# 00A-050.net
KiCad netlist of a schematic drawn in EAGLE
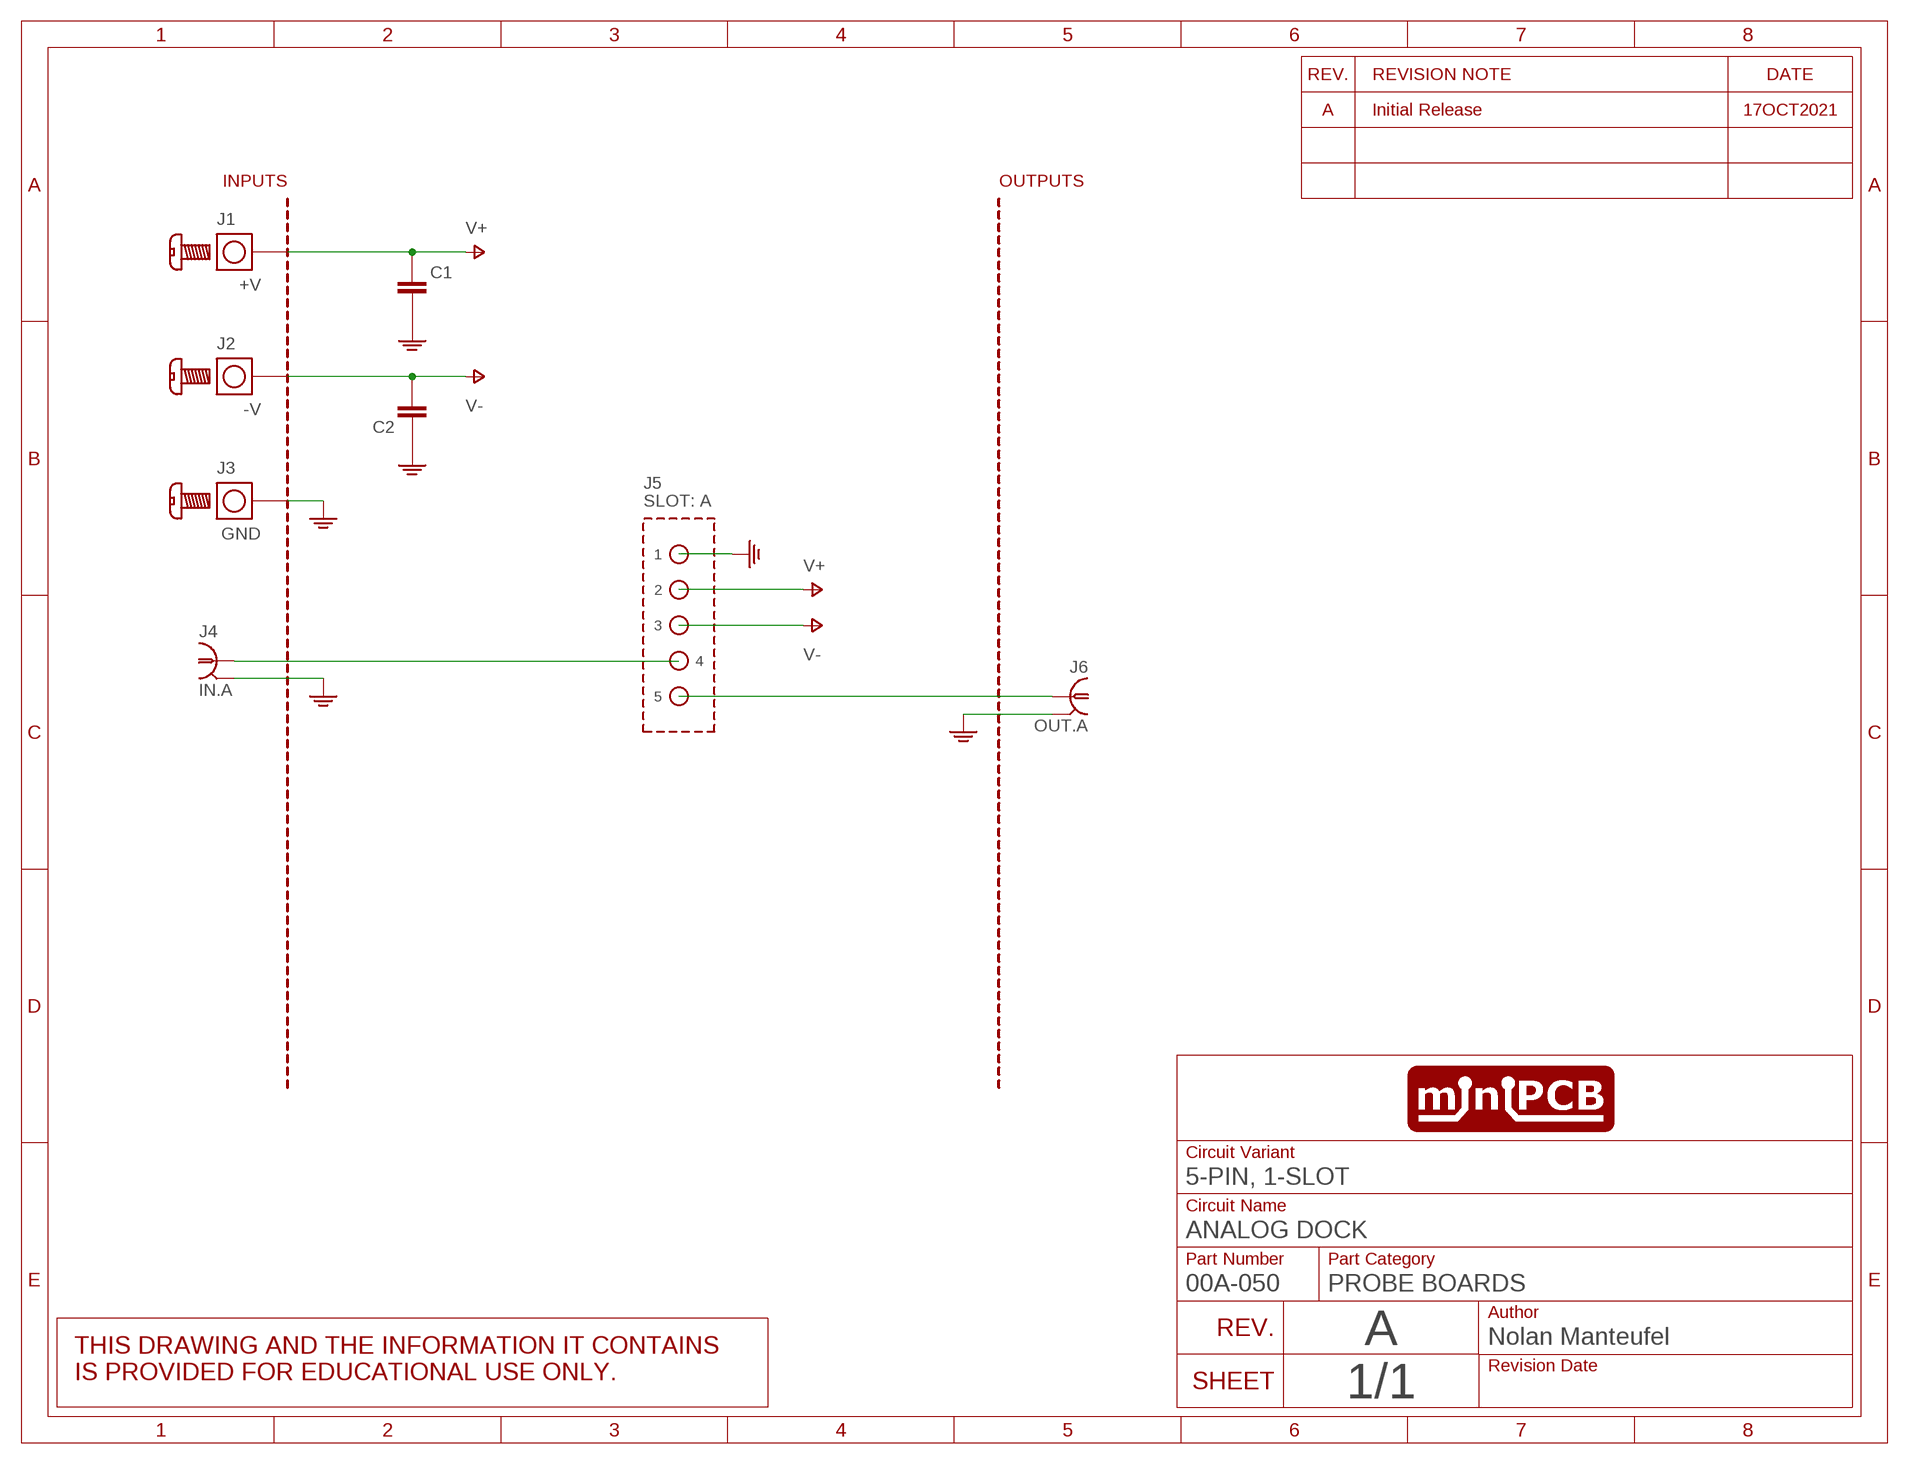
[diagram p0: schematic, sheet 1]

(export (version "E")
  (design (tool "Eeschema 10.0.6"))
  (components
    (comp (ref "C1")
      (value "CAPACITOR_10")
      (footprint "eagle-import:C5MM")
      (libsource (lib "eagle-import") (part "CAPACITOR_10"))
    )
    (comp (ref "C2")
      (value "CAPACITOR_10")
      (footprint "eagle-import:C5MM")
      (libsource (lib "eagle-import") (part "CAPACITOR_10"))
    )
    (comp (ref "J1")
      (value "+V")
      (footprint "eagle-import:SCREW-TERMINAL-M3")
      (libsource (lib "eagle-import") (part "SCREW-TERMINAL"))
    )
    (comp (ref "J2")
      (value "-V")
      (footprint "eagle-import:SCREW-TERMINAL-M3")
      (libsource (lib "eagle-import") (part "SCREW-TERMINAL"))
    )
    (comp (ref "J3")
      (value "GND")
      (footprint "eagle-import:SCREW-TERMINAL-M3")
      (libsource (lib "eagle-import") (part "SCREW-TERMINAL"))
    )
    (comp (ref "J4")
      (value "IN.A")
      (footprint "eagle-import:B35N14H")
      (libsource (lib "eagle-import") (part "BNC_35N14"))
    )
    (comp (ref "J5")
      (value "SLOT: A")
      (footprint "eagle-import:MINIPCB_DOCK_5P")
      (fields (field (name "SLOT") "A"))
      (libsource (lib "eagle-import") (part "MINIPCB_DOCK_5P_5P"))
    )
    (comp (ref "J6")
      (value "OUT.A")
      (footprint "eagle-import:B35N14H")
      (libsource (lib "eagle-import") (part "BNC_35N14"))
    )
    (comp (ref "PCB")
      (value "MINIPCB_0PDOCK_50X100")
      (footprint "eagle-import:MINIPCB_DOCK_50X100")
      (fields (field (name "PART_NUMBER") "00A-050"))
      (libsource (lib "eagle-import") (part "MINIPCB_0PDOCK_50X100"))
    )
  )
  (nets
    (net (code "1") (name "GND") (class "Default")
      (node (ref "C1") (pin "-") (pinfunction "-_-") (pintype "passive"))
      (node (ref "C2") (pin "+") (pinfunction "+_+") (pintype "passive"))
      (node (ref "J3") (pin "1") (pinfunction "1_1") (pintype "bidirectional"))
      (node (ref "J3") (pin "2") (pinfunction "1_2") (pintype "bidirectional"))
      (node (ref "J3") (pin "3") (pinfunction "1_3") (pintype "bidirectional"))
      (node (ref "J3") (pin "4") (pinfunction "1_4") (pintype "bidirectional"))
      (node (ref "J4") (pin "2.GND") (pinfunction "GND_2.GND") (pintype "power_in"))
      (node (ref "J4") (pin "3.GND") (pinfunction "GND_3.GND") (pintype "power_in"))
      (node (ref "J4") (pin "4.GND") (pinfunction "GND_4.GND") (pintype "power_in"))
      (node (ref "J4") (pin "5.GND") (pinfunction "GND_5.GND") (pintype "power_in"))
      (node (ref "J5") (pin "1") (pinfunction "1_1") (pintype "bidirectional"))
      (node (ref "J6") (pin "2.GND") (pinfunction "GND_2.GND") (pintype "power_in"))
      (node (ref "J6") (pin "3.GND") (pinfunction "GND_3.GND") (pintype "power_in"))
      (node (ref "J6") (pin "4.GND") (pinfunction "GND_4.GND") (pintype "power_in"))
      (node (ref "J6") (pin "5.GND") (pinfunction "GND_5.GND") (pintype "power_in"))
    )
    (net (code "2") (name "Net-(J4-1)") (class "Default")
      (node (ref "J4") (pin "1.SIG") (pinfunction "1_1.SIG") (pintype "passive"))
      (node (ref "J5") (pin "4") (pinfunction "4_4") (pintype "bidirectional"))
    )
    (net (code "3") (name "Net-(J6-1)") (class "Default")
      (node (ref "J5") (pin "5") (pinfunction "5_5") (pintype "bidirectional"))
      (node (ref "J6") (pin "1.SIG") (pinfunction "1_1.SIG") (pintype "passive"))
    )
    (net (code "4") (name "V+") (class "Default")
      (node (ref "C1") (pin "+") (pinfunction "+_+") (pintype "passive"))
      (node (ref "J1") (pin "1") (pinfunction "1_1") (pintype "bidirectional"))
      (node (ref "J1") (pin "2") (pinfunction "1_2") (pintype "bidirectional"))
      (node (ref "J1") (pin "3") (pinfunction "1_3") (pintype "bidirectional"))
      (node (ref "J1") (pin "4") (pinfunction "1_4") (pintype "bidirectional"))
      (node (ref "J5") (pin "2") (pinfunction "2_2") (pintype "bidirectional"))
    )
    (net (code "5") (name "V-") (class "Default")
      (node (ref "C2") (pin "-") (pinfunction "-_-") (pintype "passive"))
      (node (ref "J2") (pin "1") (pinfunction "1_1") (pintype "bidirectional"))
      (node (ref "J2") (pin "2") (pinfunction "1_2") (pintype "bidirectional"))
      (node (ref "J2") (pin "3") (pinfunction "1_3") (pintype "bidirectional"))
      (node (ref "J2") (pin "4") (pinfunction "1_4") (pintype "bidirectional"))
      (node (ref "J5") (pin "3") (pinfunction "3_3") (pintype "bidirectional"))
    )
  )
)
